# tiny84v2.net
KiCad netlist of a schematic drawn in EAGLE
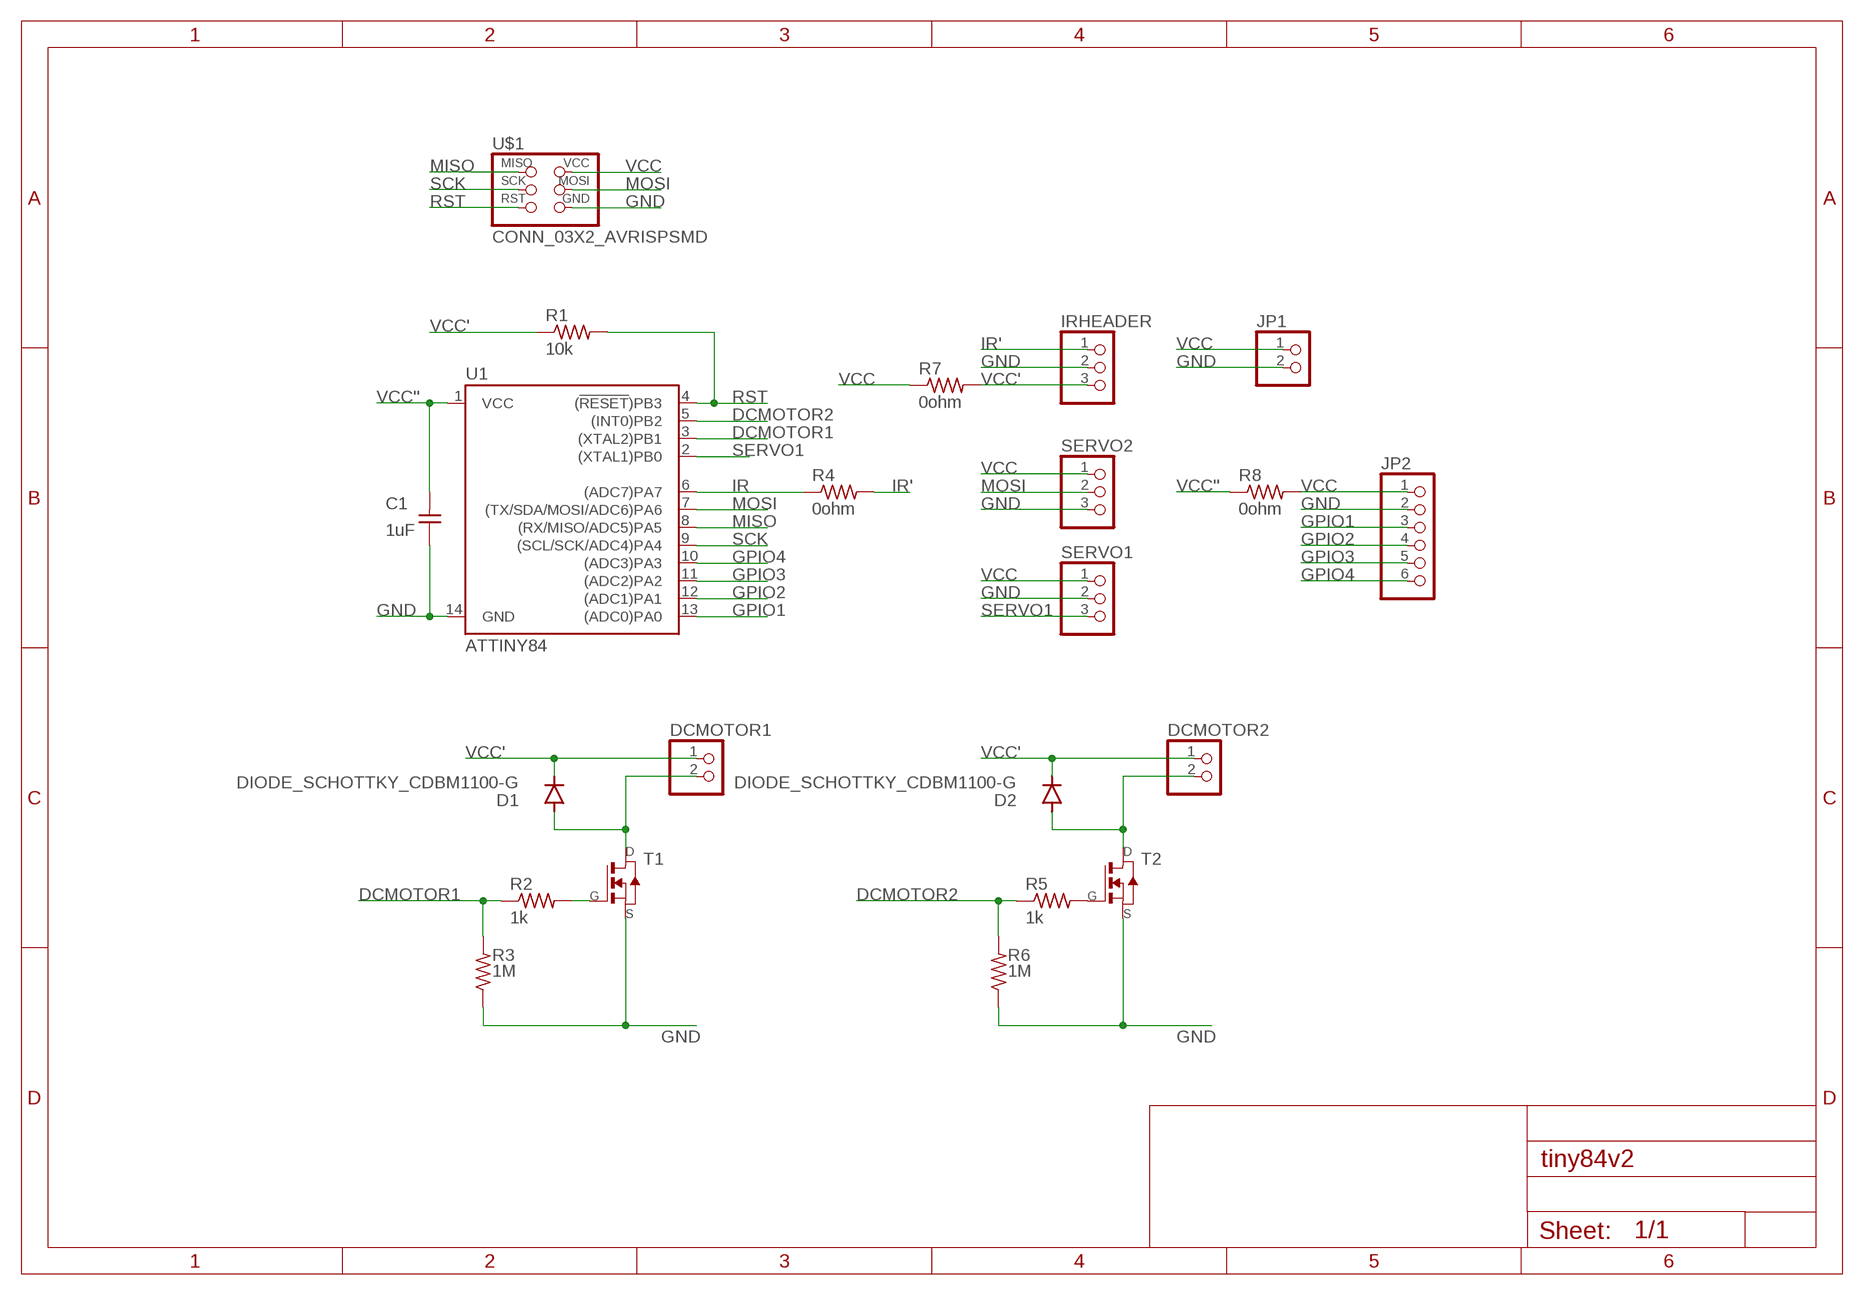
[diagram p0: schematic, sheet 1]

(export (version "E")
  (design (tool "Eeschema 10.0.6"))
  (components
    (comp (ref "C1")
      (value "1uF")
      (footprint "eagle-import:C1206FAB")
      (libsource (lib "eagle-import") (part "CAP_UNPOLARIZEDFAB"))
    )
    (comp (ref "D1")
      (value "DIODE_SCHOTTKY_CDBM1100-G")
      (footprint "eagle-import:MINI-SMA")
      (libsource (lib "eagle-import") (part "DIODE_SCHOTTKY_CDBM1100-G"))
    )
    (comp (ref "D2")
      (value "DIODE_SCHOTTKY_CDBM1100-G")
      (footprint "eagle-import:MINI-SMA")
      (libsource (lib "eagle-import") (part "DIODE_SCHOTTKY_CDBM1100-G"))
    )
    (comp (ref "DCMOTOR1")
      (value "PINHD-1X2")
      (footprint "eagle-import:1X02")
      (libsource (lib "eagle-import") (part "PINHD-1X2"))
    )
    (comp (ref "DCMOTOR2")
      (value "PINHD-1X2")
      (footprint "eagle-import:1X02")
      (libsource (lib "eagle-import") (part "PINHD-1X2"))
    )
    (comp (ref "IRHEADER")
      (value "PINHD-1X3")
      (footprint "eagle-import:1X03")
      (libsource (lib "eagle-import") (part "PINHD-1X3"))
    )
    (comp (ref "JP1")
      (value "PINHD-1X2")
      (footprint "eagle-import:1X02")
      (libsource (lib "eagle-import") (part "PINHD-1X2"))
    )
    (comp (ref "JP2")
      (value "PINHD-1X6")
      (footprint "eagle-import:1X06")
      (libsource (lib "eagle-import") (part "PINHD-1X6"))
    )
    (comp (ref "R1")
      (value "10k")
      (footprint "eagle-import:R1206FAB")
      (libsource (lib "eagle-import") (part "R1206FAB"))
    )
    (comp (ref "R2")
      (value "1k")
      (footprint "eagle-import:R1206FAB")
      (libsource (lib "eagle-import") (part "R1206FAB"))
    )
    (comp (ref "R3")
      (value "1M")
      (footprint "eagle-import:R1206FAB")
      (libsource (lib "eagle-import") (part "R1206FAB"))
    )
    (comp (ref "R4")
      (value "0ohm")
      (footprint "eagle-import:R1206FAB")
      (libsource (lib "eagle-import") (part "R1206FAB"))
    )
    (comp (ref "R5")
      (value "1k")
      (footprint "eagle-import:R1206FAB")
      (libsource (lib "eagle-import") (part "R1206FAB"))
    )
    (comp (ref "R6")
      (value "1M")
      (footprint "eagle-import:R1206FAB")
      (libsource (lib "eagle-import") (part "R1206FAB"))
    )
    (comp (ref "R7")
      (value "0ohm")
      (footprint "eagle-import:R1206FAB")
      (libsource (lib "eagle-import") (part "R1206FAB"))
    )
    (comp (ref "R8")
      (value "0ohm")
      (footprint "eagle-import:R1206FAB")
      (libsource (lib "eagle-import") (part "R1206FAB"))
    )
    (comp (ref "SERVO1")
      (value "PINHD-1X3")
      (footprint "eagle-import:1X03")
      (libsource (lib "eagle-import") (part "PINHD-1X3"))
    )
    (comp (ref "SERVO2")
      (value "PINHD-1X3")
      (footprint "eagle-import:1X03")
      (libsource (lib "eagle-import") (part "PINHD-1X3"))
    )
    (comp (ref "T1")
      (value "MOSFET_NSOT23")
      (footprint "eagle-import:SOT-23")
      (libsource (lib "eagle-import") (part "MOSFET_NSOT23"))
    )
    (comp (ref "T2")
      (value "MOSFET_NSOT23")
      (footprint "eagle-import:SOT-23")
      (libsource (lib "eagle-import") (part "MOSFET_NSOT23"))
    )
    (comp (ref "U$1")
      (value "CONN_03X2_AVRISPSMD")
      (footprint "eagle-import:2X03SMD")
      (libsource (lib "eagle-import") (part "CONN_03X2_AVRISPSMD"))
    )
    (comp (ref "U1")
      (value "ATTINY84")
      (footprint "eagle-import:SO14")
      (libsource (lib "eagle-import") (part "ATTINY84"))
    )
  )
  (nets
    (net (code "1") (name "/DCMOTOR1") (class "Default")
      (node (ref "R2") (pin "1") (pinfunction "1_1") (pintype "passive"))
      (node (ref "R3") (pin "2") (pinfunction "2_2") (pintype "passive"))
      (node (ref "U1") (pin "3") (pinfunction "(XTAL2)PB1_3") (pintype "bidirectional"))
    )
    (net (code "2") (name "/DCMOTOR2") (class "Default")
      (node (ref "R5") (pin "1") (pinfunction "1_1") (pintype "passive"))
      (node (ref "R6") (pin "2") (pinfunction "2_2") (pintype "passive"))
      (node (ref "U1") (pin "5") (pinfunction "(INT0)PB2_5") (pintype "bidirectional"))
    )
    (net (code "3") (name "/GND") (class "Default")
      (node (ref "C1") (pin "1") (pinfunction "1_1") (pintype "passive"))
      (node (ref "IRHEADER") (pin "2") (pinfunction "2_2") (pintype "passive"))
      (node (ref "JP1") (pin "2") (pinfunction "2_2") (pintype "passive"))
      (node (ref "JP2") (pin "2") (pinfunction "2_2") (pintype "passive"))
      (node (ref "R3") (pin "1") (pinfunction "1_1") (pintype "passive"))
      (node (ref "R6") (pin "1") (pinfunction "1_1") (pintype "passive"))
      (node (ref "SERVO1") (pin "2") (pinfunction "2_2") (pintype "passive"))
      (node (ref "SERVO2") (pin "3") (pinfunction "3_3") (pintype "passive"))
      (node (ref "T1") (pin "2") (pinfunction "S_2") (pintype "passive"))
      (node (ref "T2") (pin "2") (pinfunction "S_2") (pintype "passive"))
      (node (ref "U$1") (pin "6") (pinfunction "GND_6") (pintype "passive"))
      (node (ref "U1") (pin "14") (pinfunction "GND_14") (pintype "bidirectional"))
    )
    (net (code "4") (name "/GPIO1") (class "Default")
      (node (ref "JP2") (pin "3") (pinfunction "3_3") (pintype "passive"))
      (node (ref "U1") (pin "13") (pinfunction "(ADC0)PA0_13") (pintype "bidirectional"))
    )
    (net (code "5") (name "/GPIO2") (class "Default")
      (node (ref "JP2") (pin "4") (pinfunction "4_4") (pintype "passive"))
      (node (ref "U1") (pin "12") (pinfunction "(ADC1)PA1_12") (pintype "bidirectional"))
    )
    (net (code "6") (name "/GPIO3") (class "Default")
      (node (ref "JP2") (pin "5") (pinfunction "5_5") (pintype "passive"))
      (node (ref "U1") (pin "11") (pinfunction "(ADC2)PA2_11") (pintype "bidirectional"))
    )
    (net (code "7") (name "/GPIO4") (class "Default")
      (node (ref "JP2") (pin "6") (pinfunction "6_6") (pintype "passive"))
      (node (ref "U1") (pin "10") (pinfunction "(ADC3)PA3_10") (pintype "bidirectional"))
    )
    (net (code "8") (name "/IR") (class "Default")
      (node (ref "R4") (pin "1") (pinfunction "1_1") (pintype "passive"))
      (node (ref "U1") (pin "6") (pinfunction "(ADC7)PA7_6") (pintype "bidirectional"))
    )
    (net (code "9") (name "/IR'") (class "Default")
      (node (ref "IRHEADER") (pin "1") (pinfunction "1_1") (pintype "passive"))
      (node (ref "R4") (pin "2") (pinfunction "2_2") (pintype "passive"))
    )
    (net (code "10") (name "/MISO") (class "Default")
      (node (ref "U$1") (pin "1") (pinfunction "MISO_1") (pintype "passive"))
      (node (ref "U1") (pin "8") (pinfunction "(RX/MISO/ADC5)PA5_8") (pintype "bidirectional"))
    )
    (net (code "11") (name "/MOSI") (class "Default")
      (node (ref "SERVO2") (pin "2") (pinfunction "2_2") (pintype "passive"))
      (node (ref "U$1") (pin "4") (pinfunction "MOSI_4") (pintype "passive"))
      (node (ref "U1") (pin "7") (pinfunction "(TX/SDA/MOSI/ADC6)PA6_7") (pintype "bidirectional"))
    )
    (net (code "12") (name "/RST") (class "Default")
      (node (ref "R1") (pin "2") (pinfunction "2_2") (pintype "passive"))
      (node (ref "U$1") (pin "5") (pinfunction "RST_5") (pintype "passive"))
      (node (ref "U1") (pin "4") (pinfunction "(~{RESET})PB3_4") (pintype "bidirectional"))
    )
    (net (code "13") (name "/SCK") (class "Default")
      (node (ref "U$1") (pin "3") (pinfunction "SCK_3") (pintype "passive"))
      (node (ref "U1") (pin "9") (pinfunction "(SCL/SCK/ADC4)PA4_9") (pintype "bidirectional"))
    )
    (net (code "14") (name "/SERVO1") (class "Default")
      (node (ref "SERVO1") (pin "3") (pinfunction "3_3") (pintype "passive"))
      (node (ref "U1") (pin "2") (pinfunction "(XTAL1)PB0_2") (pintype "bidirectional"))
    )
    (net (code "15") (name "/VCC") (class "Default")
      (node (ref "JP1") (pin "1") (pinfunction "1_1") (pintype "passive"))
      (node (ref "JP2") (pin "1") (pinfunction "1_1") (pintype "passive"))
      (node (ref "R7") (pin "1") (pinfunction "1_1") (pintype "passive"))
      (node (ref "R8") (pin "2") (pinfunction "2_2") (pintype "passive"))
      (node (ref "SERVO1") (pin "1") (pinfunction "1_1") (pintype "passive"))
      (node (ref "SERVO2") (pin "1") (pinfunction "1_1") (pintype "passive"))
      (node (ref "U$1") (pin "2") (pinfunction "VCC_2") (pintype "passive"))
    )
    (net (code "16") (name "/VCC'") (class "Default")
      (node (ref "D1") (pin "KATHODE") (pinfunction "KATHODE_KATHODE") (pintype "bidirectional"))
      (node (ref "D2") (pin "KATHODE") (pinfunction "KATHODE_KATHODE") (pintype "bidirectional"))
      (node (ref "DCMOTOR1") (pin "1") (pinfunction "1_1") (pintype "passive"))
      (node (ref "DCMOTOR2") (pin "1") (pinfunction "1_1") (pintype "passive"))
      (node (ref "IRHEADER") (pin "3") (pinfunction "3_3") (pintype "passive"))
      (node (ref "R1") (pin "1") (pinfunction "1_1") (pintype "passive"))
      (node (ref "R7") (pin "2") (pinfunction "2_2") (pintype "passive"))
    )
    (net (code "17") (name "/VCC''") (class "Default")
      (node (ref "C1") (pin "2") (pinfunction "2_2") (pintype "passive"))
      (node (ref "R8") (pin "1") (pinfunction "1_1") (pintype "passive"))
      (node (ref "U1") (pin "1") (pinfunction "VCC_1") (pintype "bidirectional"))
    )
    (net (code "18") (name "Net-(T1-D)") (class "Default")
      (node (ref "D1") (pin "ANODE") (pinfunction "ANODE_ANODE") (pintype "bidirectional"))
      (node (ref "DCMOTOR1") (pin "2") (pinfunction "2_2") (pintype "passive"))
      (node (ref "T1") (pin "1") (pinfunction "D_1") (pintype "passive"))
    )
    (net (code "19") (name "Net-(T1-G)") (class "Default")
      (node (ref "R2") (pin "2") (pinfunction "2_2") (pintype "passive"))
      (node (ref "T1") (pin "3") (pinfunction "G_3") (pintype "passive"))
    )
    (net (code "20") (name "Net-(T2-D)") (class "Default")
      (node (ref "D2") (pin "ANODE") (pinfunction "ANODE_ANODE") (pintype "bidirectional"))
      (node (ref "DCMOTOR2") (pin "2") (pinfunction "2_2") (pintype "passive"))
      (node (ref "T2") (pin "1") (pinfunction "D_1") (pintype "passive"))
    )
    (net (code "21") (name "Net-(T2-G)") (class "Default")
      (node (ref "R5") (pin "2") (pinfunction "2_2") (pintype "passive"))
      (node (ref "T2") (pin "3") (pinfunction "G_3") (pintype "passive"))
    )
  )
)
